# Nixie_clocks_Main_board.net
KiCad netlist of a schematic drawn in Altium Designer
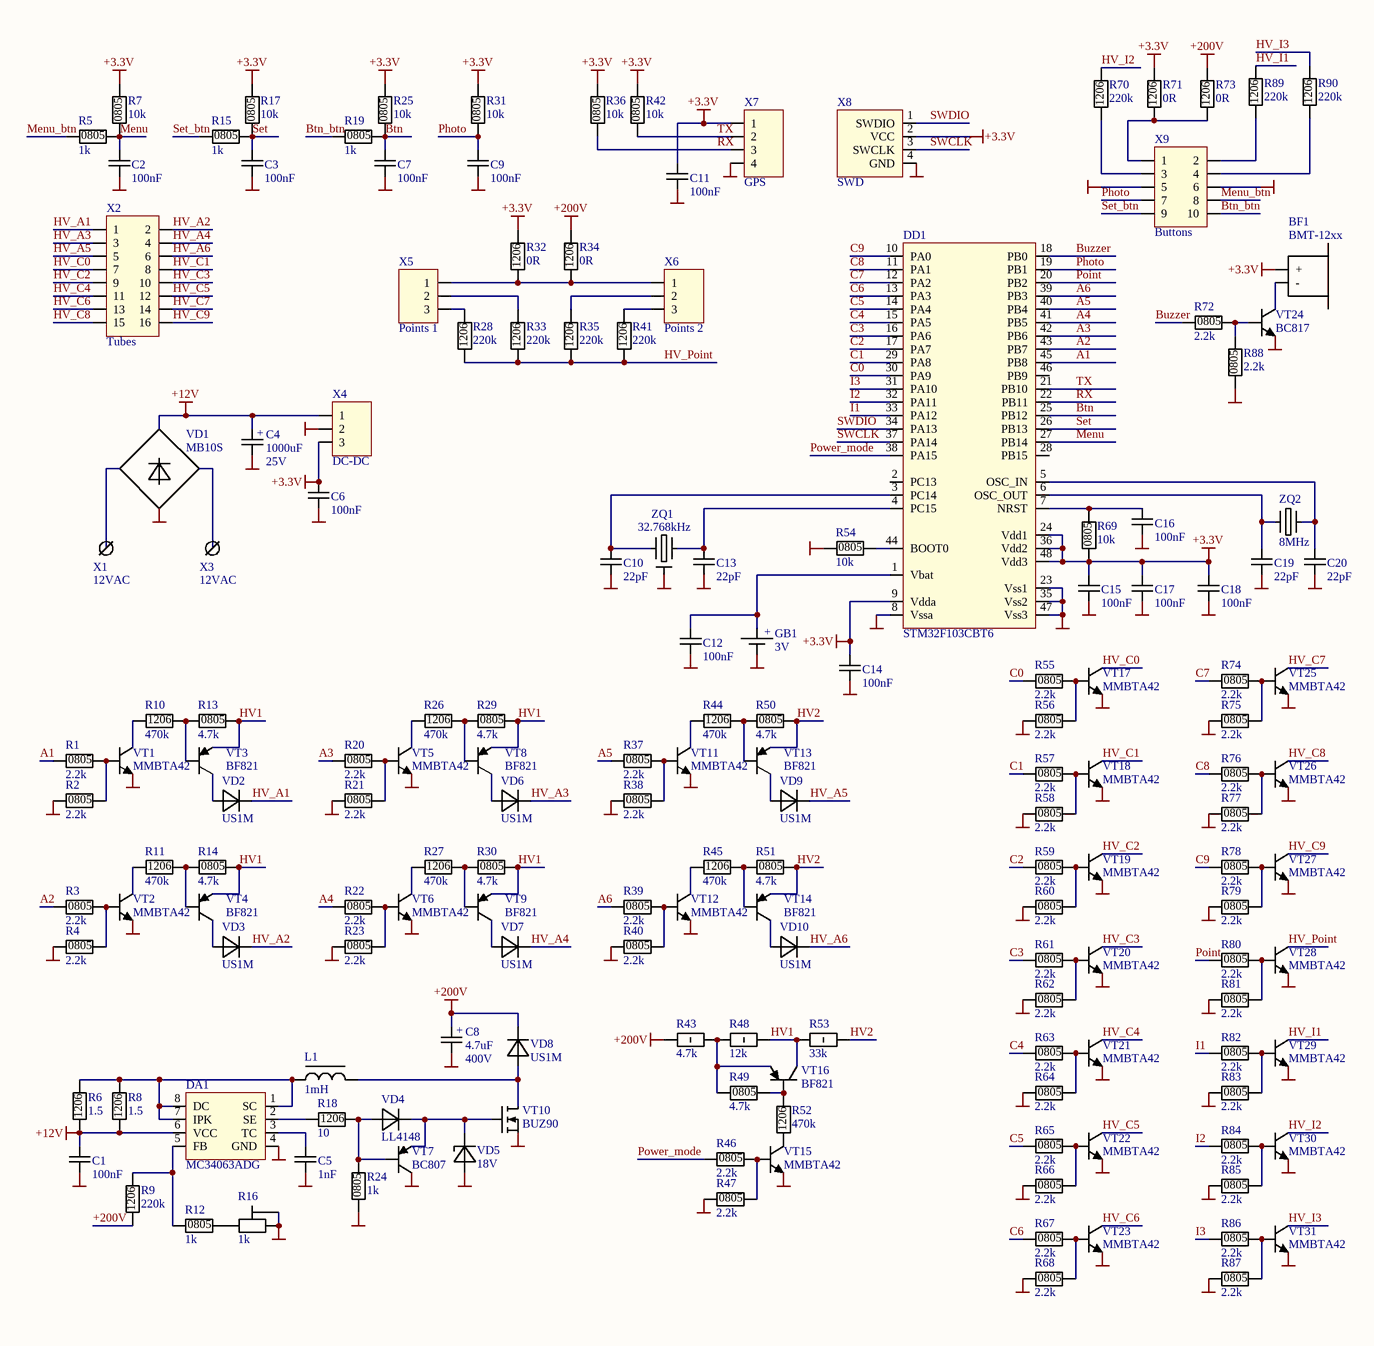
[diagram p0: Nixie_clocks_Main_board.SchDoc]

(export (version "E")
  (design (tool "Eeschema 10.0.6"))
  (components
    (comp (ref "BF1")
      (value "BMT-12xx")
      (footprint "BMT-12xx")
      (description "Magnetic transducer")
      (libsource (lib "Library") (part "Buzzer"))
    )
    (comp (ref "C1")
      (value "100nF")
      (footprint "C0805")
      (description "0805 SMD capacitors")
      (fields (field (name "PART NUMBER") "C0805"))
      (libsource (lib "Library") (part "Capacitor"))
    )
    (comp (ref "C2")
      (value "100nF")
      (footprint "C0805")
      (description "0805 SMD capacitors")
      (fields (field (name "PART NUMBER") "C0805"))
      (libsource (lib "Library") (part "Capacitor"))
    )
    (comp (ref "C3")
      (value "100nF")
      (footprint "C0805")
      (description "0805 SMD capacitors")
      (fields (field (name "PART NUMBER") "C0805"))
      (libsource (lib "Library") (part "Capacitor"))
    )
    (comp (ref "C4")
      (value "1000uF")
      (footprint "CapEl 10x20x5")
      (description "Electrolytic capacitor")
      (fields (field (name "VOLTAGE") "25V") (field (name "PART NUMBER") "CapEL_10x20x5"))
      (libsource (lib "Library") (part "CapEl"))
    )
    (comp (ref "C5")
      (value "1nF")
      (footprint "C0805")
      (description "0805 SMD capacitors")
      (fields (field (name "PART NUMBER") "C0805"))
      (libsource (lib "Library") (part "Capacitor"))
    )
    (comp (ref "C6")
      (value "100nF")
      (footprint "C0805")
      (description "0805 SMD capacitors")
      (fields (field (name "PART NUMBER") "C0805"))
      (libsource (lib "Library") (part "Capacitor"))
    )
    (comp (ref "C7")
      (value "100nF")
      (footprint "C0805")
      (description "0805 SMD capacitors")
      (fields (field (name "PART NUMBER") "C0805"))
      (libsource (lib "Library") (part "Capacitor"))
    )
    (comp (ref "C8")
      (value "4.7uF")
      (footprint "CapEl 10x20x5")
      (description "Electrolytic capacitor")
      (fields (field (name "VOLTAGE") "400V") (field (name "PART NUMBER") "CapEL_10x20x5"))
      (libsource (lib "Library") (part "CapEl"))
    )
    (comp (ref "C9")
      (value "100nF")
      (footprint "C0805")
      (description "0805 SMD capacitors")
      (fields (field (name "PART NUMBER") "C0805"))
      (libsource (lib "Library") (part "Capacitor"))
    )
    (comp (ref "C10")
      (value "22pF")
      (footprint "C0805")
      (description "0805 SMD capacitors")
      (fields (field (name "PART NUMBER") "C0805"))
      (libsource (lib "Library") (part "Capacitor"))
    )
    (comp (ref "C11")
      (value "100nF")
      (footprint "C0805")
      (description "0805 SMD capacitors")
      (fields (field (name "PART NUMBER") "C0805"))
      (libsource (lib "Library") (part "Capacitor"))
    )
    (comp (ref "C12")
      (value "100nF")
      (footprint "C0805")
      (description "0805 SMD capacitors")
      (fields (field (name "PART NUMBER") "C0805"))
      (libsource (lib "Library") (part "Capacitor"))
    )
    (comp (ref "C13")
      (value "22pF")
      (footprint "C0805")
      (description "0805 SMD capacitors")
      (fields (field (name "PART NUMBER") "C0805"))
      (libsource (lib "Library") (part "Capacitor"))
    )
    (comp (ref "C14")
      (value "100nF")
      (footprint "C0805")
      (description "0805 SMD capacitors")
      (fields (field (name "PART NUMBER") "C0805"))
      (libsource (lib "Library") (part "Capacitor"))
    )
    (comp (ref "C15")
      (value "100nF")
      (footprint "C0805")
      (description "0805 SMD capacitors")
      (fields (field (name "PART NUMBER") "C0805"))
      (libsource (lib "Library") (part "Capacitor"))
    )
    (comp (ref "C16")
      (value "100nF")
      (footprint "C0805")
      (description "0805 SMD capacitors")
      (fields (field (name "PART NUMBER") "C0805"))
      (libsource (lib "Library") (part "Capacitor"))
    )
    (comp (ref "C17")
      (value "100nF")
      (footprint "C0805")
      (description "0805 SMD capacitors")
      (fields (field (name "PART NUMBER") "C0805"))
      (libsource (lib "Library") (part "Capacitor"))
    )
    (comp (ref "C18")
      (value "100nF")
      (footprint "C0805")
      (description "0805 SMD capacitors")
      (fields (field (name "PART NUMBER") "C0805"))
      (libsource (lib "Library") (part "Capacitor"))
    )
    (comp (ref "C19")
      (value "22pF")
      (footprint "C0805")
      (description "0805 SMD capacitors")
      (fields (field (name "PART NUMBER") "C0805"))
      (libsource (lib "Library") (part "Capacitor"))
    )
    (comp (ref "C20")
      (value "22pF")
      (footprint "C0805")
      (description "0805 SMD capacitors")
      (fields (field (name "PART NUMBER") "C0805"))
      (libsource (lib "Library") (part "Capacitor"))
    )
    (comp (ref "DA1")
      (value "MC34063ADG")
      (footprint "SO8")
      (description "1.5A, Step-Up/Down/Inverting Switching Regulator")
      (libsource (lib "Library") (part "MC34063"))
    )
    (comp (ref "DD1")
      (value "STM32F103CBT6")
      (footprint "LQFP48")
      (description "ARM Cortex-M3 MCU with 128kB Flash, USB, CAN, etc.")
      (libsource (lib "Library") (part "STM32F103CBT6"))
    )
    (comp (ref "GB1")
      (value "3V")
      (footprint "CH74-2032")
      (description "Lithium CR2032 Vertical THT Battery Holder")
      (fields (field (name "PART NUMBER") "CH74-2032"))
      (libsource (lib "Library") (part "Battery"))
    )
    (comp (ref "L1")
      (value "1mH")
      (footprint "CESL inductor")
      (description "Compact energy-saving lamp inductor")
      (fields (field (name "PART NUMBER") "CESL inductor 1"))
      (libsource (lib "Library") (part "Inductor ferrite 1-4"))
    )
    (comp (ref "R1")
      (value "2.2k")
      (footprint "R0805")
      (description "0805 SMD 1/8W resistor")
      (fields (field (name "PART NUMBER") "R0805"))
      (libsource (lib "Library") (part "Resistor 0805"))
    )
    (comp (ref "R2")
      (value "2.2k")
      (footprint "R0805")
      (description "0805 SMD 1/8W resistor")
      (fields (field (name "PART NUMBER") "R0805"))
      (libsource (lib "Library") (part "Resistor 0805"))
    )
    (comp (ref "R3")
      (value "2.2k")
      (footprint "R0805")
      (description "0805 SMD 1/8W resistor")
      (fields (field (name "PART NUMBER") "R0805"))
      (libsource (lib "Library") (part "Resistor 0805"))
    )
    (comp (ref "R4")
      (value "2.2k")
      (footprint "R0805")
      (description "0805 SMD 1/8W resistor")
      (fields (field (name "PART NUMBER") "R0805"))
      (libsource (lib "Library") (part "Resistor 0805"))
    )
    (comp (ref "R5")
      (value "1k")
      (footprint "R0805")
      (description "0805 SMD 1/8W resistor")
      (fields (field (name "PART NUMBER") "R0805"))
      (libsource (lib "Library") (part "Resistor 0805"))
    )
    (comp (ref "R6")
      (value "1.5")
      (footprint "R1206")
      (description "1206 SMD 1/4W resistor")
      (fields (field (name "PART NUMBER") "R1206"))
      (libsource (lib "Library") (part "Resistor 1206"))
    )
    (comp (ref "R7")
      (value "10k")
      (footprint "R0805")
      (description "0805 SMD 1/8W resistor")
      (fields (field (name "PART NUMBER") "R0805"))
      (libsource (lib "Library") (part "Resistor 0805"))
    )
    (comp (ref "R8")
      (value "1.5")
      (footprint "R1206")
      (description "1206 SMD 1/4W resistor")
      (fields (field (name "PART NUMBER") "R1206"))
      (libsource (lib "Library") (part "Resistor 1206"))
    )
    (comp (ref "R9")
      (value "220k")
      (footprint "R1206")
      (description "1206 SMD 1/4W resistor")
      (fields (field (name "PART NUMBER") "R1206"))
      (libsource (lib "Library") (part "Resistor 1206"))
    )
    (comp (ref "R10")
      (value "470k")
      (footprint "R1206")
      (description "1206 SMD 1/4W resistor")
      (fields (field (name "PART NUMBER") "R1206"))
      (libsource (lib "Library") (part "Resistor 1206"))
    )
    (comp (ref "R11")
      (value "470k")
      (footprint "R1206")
      (description "1206 SMD 1/4W resistor")
      (fields (field (name "PART NUMBER") "R1206"))
      (libsource (lib "Library") (part "Resistor 1206"))
    )
    (comp (ref "R12")
      (value "1k")
      (footprint "R0805")
      (description "0805 SMD 1/8W resistor")
      (fields (field (name "PART NUMBER") "R0805"))
      (libsource (lib "Library") (part "Resistor 0805"))
    )
    (comp (ref "R13")
      (value "4.7k")
      (footprint "R0805")
      (description "0805 SMD 1/8W resistor")
      (fields (field (name "PART NUMBER") "R0805"))
      (libsource (lib "Library") (part "Resistor 0805"))
    )
    (comp (ref "R14")
      (value "4.7k")
      (footprint "R0805")
      (description "0805 SMD 1/8W resistor")
      (fields (field (name "PART NUMBER") "R0805"))
      (libsource (lib "Library") (part "Resistor 0805"))
    )
    (comp (ref "R15")
      (value "1k")
      (footprint "R0805")
      (description "0805 SMD 1/8W resistor")
      (fields (field (name "PART NUMBER") "R0805"))
      (libsource (lib "Library") (part "Resistor 0805"))
    )
    (comp (ref "R16")
      (value "1k")
      (footprint "3296W")
      (description "Multiturn Trimmer Resistor")
      (fields (field (name "PART NUMBER") "3296W"))
      (libsource (lib "Library") (part "Resistor Trimmer"))
    )
    (comp (ref "R17")
      (value "10k")
      (footprint "R0805")
      (description "0805 SMD 1/8W resistor")
      (fields (field (name "PART NUMBER") "R0805"))
      (libsource (lib "Library") (part "Resistor 0805"))
    )
    (comp (ref "R18")
      (value "10")
      (footprint "R1206")
      (description "1206 SMD 1/4W resistor")
      (fields (field (name "PART NUMBER") "R1206"))
      (libsource (lib "Library") (part "Resistor 1206"))
    )
    (comp (ref "R19")
      (value "1k")
      (footprint "R0805")
      (description "0805 SMD 1/8W resistor")
      (fields (field (name "PART NUMBER") "R0805"))
      (libsource (lib "Library") (part "Resistor 0805"))
    )
    (comp (ref "R20")
      (value "2.2k")
      (footprint "R0805")
      (description "0805 SMD 1/8W resistor")
      (fields (field (name "PART NUMBER") "R0805"))
      (libsource (lib "Library") (part "Resistor 0805"))
    )
    (comp (ref "R21")
      (value "2.2k")
      (footprint "R0805")
      (description "0805 SMD 1/8W resistor")
      (fields (field (name "PART NUMBER") "R0805"))
      (libsource (lib "Library") (part "Resistor 0805"))
    )
    (comp (ref "R22")
      (value "2.2k")
      (footprint "R0805")
      (description "0805 SMD 1/8W resistor")
      (fields (field (name "PART NUMBER") "R0805"))
      (libsource (lib "Library") (part "Resistor 0805"))
    )
    (comp (ref "R23")
      (value "2.2k")
      (footprint "R0805")
      (description "0805 SMD 1/8W resistor")
      (fields (field (name "PART NUMBER") "R0805"))
      (libsource (lib "Library") (part "Resistor 0805"))
    )
    (comp (ref "R24")
      (value "1k")
      (footprint "R0805")
      (description "0805 SMD 1/8W resistor")
      (fields (field (name "PART NUMBER") "R0805"))
      (libsource (lib "Library") (part "Resistor 0805"))
    )
    (comp (ref "R25")
      (value "10k")
      (footprint "R0805")
      (description "0805 SMD 1/8W resistor")
      (fields (field (name "PART NUMBER") "R0805"))
      (libsource (lib "Library") (part "Resistor 0805"))
    )
    (comp (ref "R26")
      (value "470k")
      (footprint "R1206")
      (description "1206 SMD 1/4W resistor")
      (fields (field (name "PART NUMBER") "R1206"))
      (libsource (lib "Library") (part "Resistor 1206"))
    )
    (comp (ref "R27")
      (value "470k")
      (footprint "R1206")
      (description "1206 SMD 1/4W resistor")
      (fields (field (name "PART NUMBER") "R1206"))
      (libsource (lib "Library") (part "Resistor 1206"))
    )
    (comp (ref "R28")
      (value "220k")
      (footprint "R1206")
      (description "1206 SMD 1/4W resistor")
      (fields (field (name "PART NUMBER") "R1206"))
      (libsource (lib "Library") (part "Resistor 1206"))
    )
    (comp (ref "R29")
      (value "4.7k")
      (footprint "R0805")
      (description "0805 SMD 1/8W resistor")
      (fields (field (name "PART NUMBER") "R0805"))
      (libsource (lib "Library") (part "Resistor 0805"))
    )
    (comp (ref "R30")
      (value "4.7k")
      (footprint "R0805")
      (description "0805 SMD 1/8W resistor")
      (fields (field (name "PART NUMBER") "R0805"))
      (libsource (lib "Library") (part "Resistor 0805"))
    )
    (comp (ref "R31")
      (value "10k")
      (footprint "R0805")
      (description "0805 SMD 1/8W resistor")
      (fields (field (name "PART NUMBER") "R0805"))
      (libsource (lib "Library") (part "Resistor 0805"))
    )
    (comp (ref "R32")
      (value "0R")
      (footprint "R1206")
      (description "1206 SMD 1/4W resistor")
      (fields (field (name "PART NUMBER") "R1206"))
      (libsource (lib "Library") (part "Resistor 1206"))
    )
    (comp (ref "R33")
      (value "220k")
      (footprint "R1206")
      (description "1206 SMD 1/4W resistor")
      (fields (field (name "PART NUMBER") "R1206"))
      (libsource (lib "Library") (part "Resistor 1206"))
    )
    (comp (ref "R34")
      (value "0R")
      (footprint "R1206")
      (description "1206 SMD 1/4W resistor")
      (fields (field (name "PART NUMBER") "R1206"))
      (libsource (lib "Library") (part "Resistor 1206"))
    )
    (comp (ref "R35")
      (value "220k")
      (footprint "R1206")
      (description "1206 SMD 1/4W resistor")
      (fields (field (name "PART NUMBER") "R1206"))
      (libsource (lib "Library") (part "Resistor 1206"))
    )
    (comp (ref "R36")
      (value "10k")
      (footprint "R0805")
      (description "0805 SMD 1/8W resistor")
      (fields (field (name "PART NUMBER") "R0805"))
      (libsource (lib "Library") (part "Resistor 0805"))
    )
    (comp (ref "R37")
      (value "2.2k")
      (footprint "R0805")
      (description "0805 SMD 1/8W resistor")
      (fields (field (name "PART NUMBER") "R0805"))
      (libsource (lib "Library") (part "Resistor 0805"))
    )
    (comp (ref "R38")
      (value "2.2k")
      (footprint "R0805")
      (description "0805 SMD 1/8W resistor")
      (fields (field (name "PART NUMBER") "R0805"))
      (libsource (lib "Library") (part "Resistor 0805"))
    )
    (comp (ref "R39")
      (value "2.2k")
      (footprint "R0805")
      (description "0805 SMD 1/8W resistor")
      (fields (field (name "PART NUMBER") "R0805"))
      (libsource (lib "Library") (part "Resistor 0805"))
    )
    (comp (ref "R40")
      (value "2.2k")
      (footprint "R0805")
      (description "0805 SMD 1/8W resistor")
      (fields (field (name "PART NUMBER") "R0805"))
      (libsource (lib "Library") (part "Resistor 0805"))
    )
    (comp (ref "R41")
      (value "220k")
      (footprint "R1206")
      (description "1206 SMD 1/4W resistor")
      (fields (field (name "PART NUMBER") "R1206"))
      (libsource (lib "Library") (part "Resistor 1206"))
    )
    (comp (ref "R42")
      (value "10k")
      (footprint "R0805")
      (description "0805 SMD 1/8W resistor")
      (fields (field (name "PART NUMBER") "R0805"))
      (libsource (lib "Library") (part "Resistor 0805"))
    )
    (comp (ref "R43")
      (value "4.7k")
      (footprint "MF-1W Vertical")
      (description "1W THT Resistor (Vertical mounting)")
      (fields (field (name "PART NUMBER") "MF-1WV"))
      (libsource (lib "Library") (part "Resistor 1W"))
    )
    (comp (ref "R44")
      (value "470k")
      (footprint "R1206")
      (description "1206 SMD 1/4W resistor")
      (fields (field (name "PART NUMBER") "R1206"))
      (libsource (lib "Library") (part "Resistor 1206"))
    )
    (comp (ref "R45")
      (value "470k")
      (footprint "R1206")
      (description "1206 SMD 1/4W resistor")
      (fields (field (name "PART NUMBER") "R1206"))
      (libsource (lib "Library") (part "Resistor 1206"))
    )
    (comp (ref "R46")
      (value "2.2k")
      (footprint "R0805")
      (description "0805 SMD 1/8W resistor")
      (fields (field (name "PART NUMBER") "R0805"))
      (libsource (lib "Library") (part "Resistor 0805"))
    )
    (comp (ref "R47")
      (value "2.2k")
      (footprint "R0805")
      (description "0805 SMD 1/8W resistor")
      (fields (field (name "PART NUMBER") "R0805"))
      (libsource (lib "Library") (part "Resistor 0805"))
    )
    (comp (ref "R48")
      (value "12k")
      (footprint "MF-1W Vertical")
      (description "1W THT Resistor (Vertical mounting)")
      (fields (field (name "PART NUMBER") "MF-1WV"))
      (libsource (lib "Library") (part "Resistor 1W"))
    )
    (comp (ref "R49")
      (value "4.7k")
      (footprint "R0805")
      (description "0805 SMD 1/8W resistor")
      (fields (field (name "PART NUMBER") "R0805"))
      (libsource (lib "Library") (part "Resistor 0805"))
    )
    (comp (ref "R50")
      (value "4.7k")
      (footprint "R0805")
      (description "0805 SMD 1/8W resistor")
      (fields (field (name "PART NUMBER") "R0805"))
      (libsource (lib "Library") (part "Resistor 0805"))
    )
    (comp (ref "R51")
      (value "4.7k")
      (footprint "R0805")
      (description "0805 SMD 1/8W resistor")
      (fields (field (name "PART NUMBER") "R0805"))
      (libsource (lib "Library") (part "Resistor 0805"))
    )
    (comp (ref "R52")
      (value "470k")
      (footprint "R1206")
      (description "1206 SMD 1/4W resistor")
      (fields (field (name "PART NUMBER") "R1206"))
      (libsource (lib "Library") (part "Resistor 1206"))
    )
    (comp (ref "R53")
      (value "33k")
      (footprint "MF-1W Vertical")
      (description "1W THT Resistor (Vertical mounting)")
      (fields (field (name "PART NUMBER") "MF-1WV"))
      (libsource (lib "Library") (part "Resistor 1W"))
    )
    (comp (ref "R54")
      (value "10k")
      (footprint "R0805")
      (description "0805 SMD 1/8W resistor")
      (fields (field (name "PART NUMBER") "R0805"))
      (libsource (lib "Library") (part "Resistor 0805"))
    )
    (comp (ref "R55")
      (value "2.2k")
      (footprint "R0805")
      (description "0805 SMD 1/8W resistor")
      (fields (field (name "PART NUMBER") "R0805"))
      (libsource (lib "Library") (part "Resistor 0805"))
    )
    (comp (ref "R56")
      (value "2.2k")
      (footprint "R0805")
      (description "0805 SMD 1/8W resistor")
      (fields (field (name "PART NUMBER") "R0805"))
      (libsource (lib "Library") (part "Resistor 0805"))
    )
    (comp (ref "R57")
      (value "2.2k")
      (footprint "R0805")
      (description "0805 SMD 1/8W resistor")
      (fields (field (name "PART NUMBER") "R0805"))
      (libsource (lib "Library") (part "Resistor 0805"))
    )
    (comp (ref "R58")
      (value "2.2k")
      (footprint "R0805")
      (description "0805 SMD 1/8W resistor")
      (fields (field (name "PART NUMBER") "R0805"))
      (libsource (lib "Library") (part "Resistor 0805"))
    )
    (comp (ref "R59")
      (value "2.2k")
      (footprint "R0805")
      (description "0805 SMD 1/8W resistor")
      (fields (field (name "PART NUMBER") "R0805"))
      (libsource (lib "Library") (part "Resistor 0805"))
    )
    (comp (ref "R60")
      (value "2.2k")
      (footprint "R0805")
      (description "0805 SMD 1/8W resistor")
      (fields (field (name "PART NUMBER") "R0805"))
      (libsource (lib "Library") (part "Resistor 0805"))
    )
    (comp (ref "R61")
      (value "2.2k")
      (footprint "R0805")
      (description "0805 SMD 1/8W resistor")
      (fields (field (name "PART NUMBER") "R0805"))
      (libsource (lib "Library") (part "Resistor 0805"))
    )
    (comp (ref "R62")
      (value "2.2k")
      (footprint "R0805")
      (description "0805 SMD 1/8W resistor")
      (fields (field (name "PART NUMBER") "R0805"))
      (libsource (lib "Library") (part "Resistor 0805"))
    )
    (comp (ref "R63")
      (value "2.2k")
      (footprint "R0805")
      (description "0805 SMD 1/8W resistor")
      (fields (field (name "PART NUMBER") "R0805"))
      (libsource (lib "Library") (part "Resistor 0805"))
    )
    (comp (ref "R64")
      (value "2.2k")
      (footprint "R0805")
      (description "0805 SMD 1/8W resistor")
      (fields (field (name "PART NUMBER") "R0805"))
      (libsource (lib "Library") (part "Resistor 0805"))
    )
    (comp (ref "R65")
      (value "2.2k")
      (footprint "R0805")
      (description "0805 SMD 1/8W resistor")
      (fields (field (name "PART NUMBER") "R0805"))
      (libsource (lib "Library") (part "Resistor 0805"))
    )
    (comp (ref "R66")
      (value "2.2k")
      (footprint "R0805")
      (description "0805 SMD 1/8W resistor")
      (fields (field (name "PART NUMBER") "R0805"))
      (libsource (lib "Library") (part "Resistor 0805"))
    )
    (comp (ref "R67")
      (value "2.2k")
      (footprint "R0805")
      (description "0805 SMD 1/8W resistor")
      (fields (field (name "PART NUMBER") "R0805"))
      (libsource (lib "Library") (part "Resistor 0805"))
    )
    (comp (ref "R68")
      (value "2.2k")
      (footprint "R0805")
      (description "0805 SMD 1/8W resistor")
      (fields (field (name "PART NUMBER") "R0805"))
      (libsource (lib "Library") (part "Resistor 0805"))
    )
    (comp (ref "R69")
      (value "10k")
      (footprint "R0805")
      (description "0805 SMD 1/8W resistor")
      (fields (field (name "PART NUMBER") "R0805"))
      (libsource (lib "Library") (part "Resistor 0805"))
    )
    (comp (ref "R70")
      (value "220k")
      (footprint "R1206")
      (description "1206 SMD 1/4W resistor")
      (fields (field (name "PART NUMBER") "R1206"))
      (libsource (lib "Library") (part "Resistor 1206"))
    )
    (comp (ref "R71")
      (value "0R")
      (footprint "R1206")
      (description "1206 SMD 1/4W resistor")
      (fields (field (name "PART NUMBER") "R1206"))
      (libsource (lib "Library") (part "Resistor 1206"))
    )
    (comp (ref "R72")
      (value "2.2k")
      (footprint "R0805")
      (description "0805 SMD 1/8W resistor")
      (fields (field (name "PART NUMBER") "R0805"))
      (libsource (lib "Library") (part "Resistor 0805"))
    )
    (comp (ref "R73")
      (value "0R")
      (footprint "R1206")
      (description "1206 SMD 1/4W resistor")
      (fields (field (name "PART NUMBER") "R1206"))
      (libsource (lib "Library") (part "Resistor 1206"))
    )
    (comp (ref "R74")
      (value "2.2k")
      (footprint "R0805")
      (description "0805 SMD 1/8W resistor")
      (fields (field (name "PART NUMBER") "R0805"))
      (libsource (lib "Library") (part "Resistor 0805"))
    )
    (comp (ref "R75")
      (value "2.2k")
      (footprint "R0805")
      (description "0805 SMD 1/8W resistor")
      (fields (field (name "PART NUMBER") "R0805"))
      (libsource (lib "Library") (part "Resistor 0805"))
    )
    (comp (ref "R76")
      (value "2.2k")
      (footprint "R0805")
      (description "0805 SMD 1/8W resistor")
      (fields (field (name "PART NUMBER") "R0805"))
      (libsource (lib "Library") (part "Resistor 0805"))
    )
    (comp (ref "R77")
      (value "2.2k")
      (footprint "R0805")
      (description "0805 SMD 1/8W resistor")
      (fields (field (name "PART NUMBER") "R0805"))
      (libsource (lib "Library") (part "Resistor 0805"))
    )
    (comp (ref "R78")
      (value "2.2k")
      (footprint "R0805")
      (description "0805 SMD 1/8W resistor")
      (fields (field (name "PART NUMBER") "R0805"))
      (libsource (lib "Library") (part "Resistor 0805"))
    )
    (comp (ref "R79")
      (value "2.2k")
      (footprint "R0805")
      (description "0805 SMD 1/8W resistor")
      (fields (field (name "PART NUMBER") "R0805"))
      (libsource (lib "Library") (part "Resistor 0805"))
    )
    (comp (ref "R80")
      (value "2.2k")
      (footprint "R0805")
      (description "0805 SMD 1/8W resistor")
      (fields (field (name "PART NUMBER") "R0805"))
      (libsource (lib "Library") (part "Resistor 0805"))
    )
    (comp (ref "R81")
      (value "2.2k")
      (footprint "R0805")
      (description "0805 SMD 1/8W resistor")
      (fields (field (name "PART NUMBER") "R0805"))
      (libsource (lib "Library") (part "Resistor 0805"))
    )
    (comp (ref "R82")
      (value "2.2k")
      (footprint "R0805")
      (description "0805 SMD 1/8W resistor")
      (fields (field (name "PART NUMBER") "R0805"))
      (libsource (lib "Library") (part "Resistor 0805"))
    )
    (comp (ref "R83")
      (value "2.2k")
      (footprint "R0805")
      (description "0805 SMD 1/8W resistor")
      (fields (field (name "PART NUMBER") "R0805"))
      (libsource (lib "Library") (part "Resistor 0805"))
    )
    (comp (ref "R84")
      (value "2.2k")
      (footprint "R0805")
      (description "0805 SMD 1/8W resistor")
      (fields (field (name "PART NUMBER") "R0805"))
      (libsource (lib "Library") (part "Resistor 0805"))
    )
    (comp (ref "R85")
      (value "2.2k")
      (footprint "R0805")
      (description "0805 SMD 1/8W resistor")
      (fields (field (name "PART NUMBER") "R0805"))
      (libsource (lib "Library") (part "Resistor 0805"))
    )
    (comp (ref "R86")
      (value "2.2k")
      (footprint "R0805")
      (description "0805 SMD 1/8W resistor")
      (fields (field (name "PART NUMBER") "R0805"))
      (libsource (lib "Library") (part "Resistor 0805"))
    )
    (comp (ref "R87")
      (value "2.2k")
      (footprint "R0805")
      (description "0805 SMD 1/8W resistor")
      (fields (field (name "PART NUMBER") "R0805"))
      (libsource (lib "Library") (part "Resistor 0805"))
    )
    (comp (ref "R88")
      (value "2.2k")
      (footprint "R0805")
      (description "0805 SMD 1/8W resistor")
      (fields (field (name "PART NUMBER") "R0805"))
      (libsource (lib "Library") (part "Resistor 0805"))
    )
    (comp (ref "R89")
      (value "220k")
      (footprint "R1206")
      (description "1206 SMD 1/4W resistor")
      (fields (field (name "PART NUMBER") "R1206"))
      (libsource (lib "Library") (part "Resistor 1206"))
    )
    (comp (ref "R90")
      (value "220k")
      (footprint "R1206")
      (description "1206 SMD 1/4W resistor")
      (fields (field (name "PART NUMBER") "R1206"))
      (libsource (lib "Library") (part "Resistor 1206"))
    )
    (comp (ref "VD1")
      (value "MB10S")
      (footprint "MBS")
      (description "Single-Phase Silicon Bridge Rectifier")
      (libsource (lib "Library") (part "Diode Bridge"))
    )
    (comp (ref "VD2")
      (value "US1M")
      (footprint "SMA")
      (description "Surface Mount Ultrafast Rectifier")
      (libsource (lib "Library") (part "Diode"))
    )
    (comp (ref "VD3")
      (value "US1M")
      (footprint "SMA")
      (description "Surface Mount Ultrafast Rectifier")
      (libsource (lib "Library") (part "Diode"))
    )
    (comp (ref "VD4")
      (value "LL4148")
      (footprint "SOD80")
      (description "75V 150mA Small Signal Fast Switching Diode")
      (libsource (lib "Library") (part "Diode"))
    )
    (comp (ref "VD5")
      (value "18V")
      (footprint "SOD80")
      (description "500mW SMD Zener Diode")
      (fields (field (name "PART NUMBER") "BZV55"))
      (libsource (lib "Library") (part "Diode Zener"))
    )
    (comp (ref "VD6")
      (value "US1M")
      (footprint "SMA")
      (description "Surface Mount Ultrafast Rectifier")
      (libsource (lib "Library") (part "Diode"))
    )
    (comp (ref "VD7")
      (value "US1M")
      (footprint "SMA")
      (description "Surface Mount Ultrafast Rectifier")
      (libsource (lib "Library") (part "Diode"))
    )
    (comp (ref "VD8")
      (value "US1M")
      (footprint "SMA")
      (description "Surface Mount Ultrafast Rectifier")
      (libsource (lib "Library") (part "Diode"))
    )
    (comp (ref "VD9")
      (value "US1M")
      (footprint "SMA")
      (description "Surface Mount Ultrafast Rectifier")
      (libsource (lib "Library") (part "Diode"))
    )
    (comp (ref "VD10")
      (value "US1M")
      (footprint "SMA")
      (description "Surface Mount Ultrafast Rectifier")
      (libsource (lib "Library") (part "Diode"))
    )
    (comp (ref "VT1")
      (value "MMBTA42")
      (footprint "SOT23-3")
      (description "300V 500mA SOT23-3 SMD NPN transistor with h21>25")
      (libsource (lib "Library") (part "NPN_BEC"))
    )
    (comp (ref "VT2")
      (value "MMBTA42")
      (footprint "SOT23-3")
      (description "300V 500mA SOT23-3 SMD NPN transistor with h21>25")
      (libsource (lib "Library") (part "NPN_BEC"))
    )
    (comp (ref "VT3")
      (value "BF821")
      (footprint "SOT23-3")
      (description "300V 50mA SOT23-3 SMD PNP transistor with h21>50")
      (libsource (lib "Library") (part "PNP_BEC"))
    )
    (comp (ref "VT4")
      (value "BF821")
      (footprint "SOT23-3")
      (description "300V 50mA SOT23-3 SMD PNP transistor with h21>50")
      (libsource (lib "Library") (part "PNP_BEC"))
    )
    (comp (ref "VT5")
      (value "MMBTA42")
      (footprint "SOT23-3")
      (description "300V 500mA SOT23-3 SMD NPN transistor with h21>25")
      (libsource (lib "Library") (part "NPN_BEC"))
    )
    (comp (ref "VT6")
      (value "MMBTA42")
      (footprint "SOT23-3")
      (description "300V 500mA SOT23-3 SMD NPN transistor with h21>25")
      (libsource (lib "Library") (part "NPN_BEC"))
    )
    (comp (ref "VT7")
      (value "BC807")
      (footprint "SOT23-3")
      (description "45V 500mA SOT23-3 SMD PNP transistor with h21>100")
      (libsource (lib "Library") (part "PNP_BEC"))
    )
    (comp (ref "VT8")
      (value "BF821")
      (footprint "SOT23-3")
      (description "300V 50mA SOT23-3 SMD PNP transistor with h21>50")
      (libsource (lib "Library") (part "PNP_BEC"))
    )
    (comp (ref "VT9")
      (value "BF821")
      (footprint "SOT23-3")
      (description "300V 50mA SOT23-3 SMD PNP transistor with h21>50")
      (libsource (lib "Library") (part "PNP_BEC"))
    )
    (comp (ref "VT10")
      (value "BUZ90")
      (footprint "TO220-3")
      (description "600V 4.5A TO220-3 THT n-MOSFET transistor")
      (libsource (lib "Library") (part "NMOSFET_GDS"))
    )
    (comp (ref "VT11")
      (value "MMBTA42")
      (footprint "SOT23-3")
      (description "300V 500mA SOT23-3 SMD NPN transistor with h21>25")
      (libsource (lib "Library") (part "NPN_BEC"))
    )
    (comp (ref "VT12")
      (value "MMBTA42")
      (footprint "SOT23-3")
      (description "300V 500mA SOT23-3 SMD NPN transistor with h21>25")
      (libsource (lib "Library") (part "NPN_BEC"))
    )
    (comp (ref "VT13")
      (value "BF821")
      (footprint "SOT23-3")
      (description "300V 50mA SOT23-3 SMD PNP transistor with h21>50")
      (libsource (lib "Library") (part "PNP_BEC"))
    )
    (comp (ref "VT14")
      (value "BF821")
      (footprint "SOT23-3")
      (description "300V 50mA SOT23-3 SMD PNP transistor with h21>50")
      (libsource (lib "Library") (part "PNP_BEC"))
    )
    (comp (ref "VT15")
      (value "MMBTA42")
      (footprint "SOT23-3")
      (description "300V 500mA SOT23-3 SMD NPN transistor with h21>25")
      (libsource (lib "Library") (part "NPN_BEC"))
    )
    (comp (ref "VT16")
      (value "BF821")
      (footprint "SOT23-3")
      (description "300V 50mA SOT23-3 SMD PNP transistor with h21>50")
      (libsource (lib "Library") (part "PNP_BEC"))
    )
    (comp (ref "VT17")
      (value "MMBTA42")
      (footprint "SOT23-3")
      (description "300V 500mA SOT23-3 SMD NPN transistor with h21>25")
      (libsource (lib "Library") (part "NPN_BEC"))
    )
    (comp (ref "VT18")
      (value "MMBTA42")
      (footprint "SOT23-3")
      (description "300V 500mA SOT23-3 SMD NPN transistor with h21>25")
      (libsource (lib "Library") (part "NPN_BEC"))
    )
    (comp (ref "VT19")
      (value "MMBTA42")
      (footprint "SOT23-3")
      (description "300V 500mA SOT23-3 SMD NPN transistor with h21>25")
      (libsource (lib "Library") (part "NPN_BEC"))
    )
    (comp (ref "VT20")
      (value "MMBTA42")
      (footprint "SOT23-3")
      (description "300V 500mA SOT23-3 SMD NPN transistor with h21>25")
      (libsource (lib "Library") (part "NPN_BEC"))
    )
    (comp (ref "VT21")
      (value "MMBTA42")
      (footprint "SOT23-3")
      (description "300V 500mA SOT23-3 SMD NPN transistor with h21>25")
      (libsource (lib "Library") (part "NPN_BEC"))
    )
    (comp (ref "VT22")
      (value "MMBTA42")
      (footprint "SOT23-3")
      (description "300V 500mA SOT23-3 SMD NPN transistor with h21>25")
      (libsource (lib "Library") (part "NPN_BEC"))
    )
    (comp (ref "VT23")
      (value "MMBTA42")
      (footprint "SOT23-3")
      (description "300V 500mA SOT23-3 SMD NPN transistor with h21>25")
      (libsource (lib "Library") (part "NPN_BEC"))
    )
    (comp (ref "VT24")
      (value "BC817")
      (footprint "SOT23-3")
      (description "45V 500mA SOT23-3 SMD NPN transistor with h21>100")
      (libsource (lib "Library") (part "NPN_BEC"))
    )
    (comp (ref "VT25")
      (value "MMBTA42")
      (footprint "SOT23-3")
      (description "300V 500mA SOT23-3 SMD NPN transistor with h21>25")
      (libsource (lib "Library") (part "NPN_BEC"))
    )
    (comp (ref "VT26")
      (value "MMBTA42")
      (footprint "SOT23-3")
      (description "300V 500mA SOT23-3 SMD NPN transistor with h21>25")
      (libsource (lib "Library") (part "NPN_BEC"))
    )
    (comp (ref "VT27")
      (value "MMBTA42")
      (footprint "SOT23-3")
      (description "300V 500mA SOT23-3 SMD NPN transistor with h21>25")
      (libsource (lib "Library") (part "NPN_BEC"))
    )
    (comp (ref "VT28")
      (value "MMBTA42")
      (footprint "SOT23-3")
      (description "300V 500mA SOT23-3 SMD NPN transistor with h21>25")
      (libsource (lib "Library") (part "NPN_BEC"))
    )
    (comp (ref "VT29")
      (value "MMBTA42")
      (footprint "SOT23-3")
      (description "300V 500mA SOT23-3 SMD NPN transistor with h21>25")
      (libsource (lib "Library") (part "NPN_BEC"))
    )
    (comp (ref "VT30")
      (value "MMBTA42")
      (footprint "SOT23-3")
      (description "300V 500mA SOT23-3 SMD NPN transistor with h21>25")
      (libsource (lib "Library") (part "NPN_BEC"))
    )
    (comp (ref "VT31")
      (value "MMBTA42")
      (footprint "SOT23-3")
      (description "300V 500mA SOT23-3 SMD NPN transistor with h21>25")
      (libsource (lib "Library") (part "NPN_BEC"))
    )
    (comp (ref "X1")
      (value "12VAC")
      (footprint "Terminal_2,8")
      (description "Terminal")
      (fields (field (name "PART NUMBER") "Term_2.8"))
      (libsource (lib "Library") (part "Terminal"))
    )
    (comp (ref "X2")
      (value "Tubes")
      (footprint "IDC16")
      (description "PCB Connector")
      (fields (field (name "PART NUMBER") "IDC-16"))
      (libsource (lib "Library") (part "IDC16"))
    )
    (comp (ref "X3")
      (value "12VAC")
      (footprint "Terminal_2,8")
      (description "Terminal")
      (fields (field (name "PART NUMBER") "Term_2.8"))
      (libsource (lib "Library") (part "Terminal"))
    )
    (comp (ref "X4")
      (value "DC-DC")
      (footprint "PBS3")
      (description "PCB Connector")
      (fields (field (name "PART NUMBER") "PBS-3"))
      (libsource (lib "Library") (part "Connector 3 pin"))
    )
    (comp (ref "X5")
      (value "Points 1")
      (footprint "WF-3")
      (description "PCB Connector")
      (fields (field (name "PART NUMBER") "WF-3"))
      (libsource (lib "") (part "Connector 3 pin_1"))
    )
    (comp (ref "X6")
      (value "Points 2")
      (footprint "WF-3")
      (description "PCB Connector")
      (fields (field (name "PART NUMBER") "WF-3"))
      (libsource (lib "Library") (part "Connector 3 pin"))
    )
    (comp (ref "X7")
      (value "GPS")
      (footprint "WF-4")
      (description "PCB Connector")
      (fields (field (name "PART NUMBER") "WF-4"))
      (libsource (lib "Library") (part "Connector 4 pin"))
    )
    (comp (ref "X8")
      (value "SWD")
      (footprint "PLS4")
      (description "4 pin SWD connector for ARM MCU programming")
      (libsource (lib "Library") (part "Connector SWD"))
    )
    (comp (ref "X9")
      (value "Buttons")
      (footprint "IDC10")
      (description "PCB Connector")
      (fields (field (name "PART NUMBER") "IDC-10"))
      (libsource (lib "Library") (part "IDC10"))
    )
    (comp (ref "ZQ1")
      (value "32.768kHz")
      (footprint "DT-38")
      (description "RTC THT Quartz Resonator")
      (fields (field (name "PART NUMBER") "DT-38"))
      (libsource (lib "Library") (part "Quartz grounded"))
    )
    (comp (ref "ZQ2")
      (value "8MHz")
      (footprint "HC49SM")
      (description "Standard SMD Quartz Resonator")
      (fields (field (name "PART NUMBER") "HC49SM"))
      (libsource (lib "Library") (part "Quartz"))
    )
  )
  (nets
    (net (code "1") (name "+3.3V") (class "Default")
      (node (ref "BF1") (pin "1") (pinfunction "+_1") (pintype "passive"))
      (node (ref "C11") (pin "2") (pinfunction "2_2") (pintype "passive"))
      (node (ref "C14") (pin "2") (pinfunction "2_2") (pintype "passive"))
      (node (ref "C15") (pin "2") (pinfunction "2_2") (pintype "passive"))
      (node (ref "C17") (pin "2") (pinfunction "2_2") (pintype "passive"))
      (node (ref "C18") (pin "2") (pinfunction "2_2") (pintype "passive"))
      (node (ref "C6") (pin "2") (pinfunction "2_2") (pintype "passive"))
      (node (ref "DD1") (pin "24") (pinfunction "Vdd1_24") (pintype "passive"))
      (node (ref "DD1") (pin "36") (pinfunction "Vdd2_36") (pintype "passive"))
      (node (ref "DD1") (pin "48") (pinfunction "Vdd3_48") (pintype "passive"))
      (node (ref "DD1") (pin "9") (pinfunction "Vdda_9") (pintype "passive"))
      (node (ref "R17") (pin "2") (pinfunction "2_2") (pintype "passive"))
      (node (ref "R25") (pin "2") (pinfunction "2_2") (pintype "passive"))
      (node (ref "R31") (pin "2") (pinfunction "2_2") (pintype "passive"))
      (node (ref "R32") (pin "2") (pinfunction "2_2") (pintype "passive"))
      (node (ref "R36") (pin "2") (pinfunction "2_2") (pintype "passive"))
      (node (ref "R42") (pin "2") (pinfunction "2_2") (pintype "passive"))
      (node (ref "R69") (pin "1") (pinfunction "1_1") (pintype "passive"))
      (node (ref "R7") (pin "2") (pinfunction "2_2") (pintype "passive"))
      (node (ref "R71") (pin "2") (pinfunction "2_2") (pintype "passive"))
      (node (ref "X4") (pin "3") (pinfunction "3_3") (pintype "passive"))
      (node (ref "X7") (pin "1") (pinfunction "1_1") (pintype "passive"))
      (node (ref "X8") (pin "2") (pinfunction "VCC_2") (pintype "passive"))
    )
    (net (code "2") (name "+12V") (class "Default")
      (node (ref "C1") (pin "2") (pinfunction "2_2") (pintype "passive"))
      (node (ref "C4") (pin "1") (pinfunction "1_1") (pintype "passive"))
      (node (ref "DA1") (pin "6") (pinfunction "VCC_6") (pintype "passive"))
      (node (ref "R6") (pin "1") (pinfunction "1_1") (pintype "passive"))
      (node (ref "R8") (pin "1") (pinfunction "1_1") (pintype "passive"))
      (node (ref "VD1") (pin "1") (pinfunction "+U_1") (pintype "passive"))
      (node (ref "X4") (pin "1") (pinfunction "1_1") (pintype "passive"))
    )
    (net (code "3") (name "+200V") (class "Default")
      (node (ref "C8") (pin "1") (pinfunction "1_1") (pintype "passive"))
      (node (ref "R34") (pin "2") (pinfunction "2_2") (pintype "passive"))
      (node (ref "R43") (pin "1") (pinfunction "1_1") (pintype "passive"))
      (node (ref "R73") (pin "2") (pinfunction "2_2") (pintype "passive"))
      (node (ref "R9") (pin "1") (pinfunction "1_1") (pintype "passive"))
      (node (ref "VD8") (pin "2") (pinfunction "K_2") (pintype "passive"))
    )
    (net (code "4") (name "/A1") (class "Default")
      (node (ref "DD1") (pin "45") (pinfunction "PB8_45") (pintype "passive"))
      (node (ref "R1") (pin "1") (pinfunction "1_1") (pintype "passive"))
    )
    (net (code "5") (name "/A2") (class "Default")
      (node (ref "DD1") (pin "43") (pinfunction "PB7_43") (pintype "passive"))
      (node (ref "R3") (pin "1") (pinfunction "1_1") (pintype "passive"))
    )
    (net (code "6") (name "/A3") (class "Default")
      (node (ref "DD1") (pin "42") (pinfunction "PB6_42") (pintype "passive"))
      (node (ref "R20") (pin "1") (pinfunction "1_1") (pintype "passive"))
    )
    (net (code "7") (name "/A4") (class "Default")
      (node (ref "DD1") (pin "41") (pinfunction "PB5_41") (pintype "passive"))
      (node (ref "R22") (pin "1") (pinfunction "1_1") (pintype "passive"))
    )
    (net (code "8") (name "/A5") (class "Default")
      (node (ref "DD1") (pin "40") (pinfunction "PB4_40") (pintype "passive"))
      (node (ref "R37") (pin "1") (pinfunction "1_1") (pintype "passive"))
    )
    (net (code "9") (name "/A6") (class "Default")
      (node (ref "DD1") (pin "39") (pinfunction "PB3_39") (pintype "passive"))
      (node (ref "R39") (pin "1") (pinfunction "1_1") (pintype "passive"))
    )
    (net (code "10") (name "/Btn") (class "Default")
      (node (ref "C7") (pin "2") (pinfunction "2_2") (pintype "passive"))
      (node (ref "DD1") (pin "25") (pinfunction "PB12_25") (pintype "passive"))
      (node (ref "R19") (pin "2") (pinfunction "2_2") (pintype "passive"))
      (node (ref "R25") (pin "1") (pinfunction "1_1") (pintype "passive"))
    )
    (net (code "11") (name "/Btn_btn") (class "Default")
      (node (ref "R19") (pin "1") (pinfunction "1_1") (pintype "passive"))
      (node (ref "X9") (pin "10") (pinfunction "10_10") (pintype "passive"))
    )
    (net (code "12") (name "/Buzzer") (class "Default")
      (node (ref "DD1") (pin "18") (pinfunction "PB0_18") (pintype "passive"))
      (node (ref "R72") (pin "1") (pinfunction "1_1") (pintype "passive"))
    )
    (net (code "13") (name "/C0") (class "Default")
      (node (ref "DD1") (pin "30") (pinfunction "PA9_30") (pintype "passive"))
      (node (ref "R55") (pin "1") (pinfunction "1_1") (pintype "passive"))
    )
    (net (code "14") (name "/C1") (class "Default")
      (node (ref "DD1") (pin "29") (pinfunction "PA8_29") (pintype "passive"))
      (node (ref "R57") (pin "1") (pinfunction "1_1") (pintype "passive"))
    )
    (net (code "15") (name "/C2") (class "Default")
      (node (ref "DD1") (pin "17") (pinfunction "PA7_17") (pintype "passive"))
      (node (ref "R59") (pin "1") (pinfunction "1_1") (pintype "passive"))
    )
    (net (code "16") (name "/C3") (class "Default")
      (node (ref "DD1") (pin "16") (pinfunction "PA6_16") (pintype "passive"))
      (node (ref "R61") (pin "1") (pinfunction "1_1") (pintype "passive"))
    )
    (net (code "17") (name "/C4") (class "Default")
      (node (ref "DD1") (pin "15") (pinfunction "PA5_15") (pintype "passive"))
      (node (ref "R63") (pin "1") (pinfunction "1_1") (pintype "passive"))
    )
    (net (code "18") (name "/C5") (class "Default")
      (node (ref "DD1") (pin "14") (pinfunction "PA4_14") (pintype "passive"))
      (node (ref "R65") (pin "1") (pinfunction "1_1") (pintype "passive"))
    )
    (net (code "19") (name "/C6") (class "Default")
      (node (ref "DD1") (pin "13") (pinfunction "PA3_13") (pintype "passive"))
      (node (ref "R67") (pin "1") (pinfunction "1_1") (pintype "passive"))
    )
    (net (code "20") (name "/C7") (class "Default")
      (node (ref "DD1") (pin "12") (pinfunction "PA2_12") (pintype "passive"))
      (node (ref "R74") (pin "1") (pinfunction "1_1") (pintype "passive"))
    )
    (net (code "21") (name "/C8") (class "Default")
      (node (ref "DD1") (pin "11") (pinfunction "PA1_11") (pintype "passive"))
      (node (ref "R76") (pin "1") (pinfunction "1_1") (pintype "passive"))
    )
    (net (code "22") (name "/C9") (class "Default")
      (node (ref "DD1") (pin "10") (pinfunction "PA0_10") (pintype "passive"))
      (node (ref "R78") (pin "1") (pinfunction "1_1") (pintype "passive"))
    )
    (net (code "23") (name "/HV1") (class "Default")
      (node (ref "R13") (pin "2") (pinfunction "2_2") (pintype "passive"))
      (node (ref "R14") (pin "2") (pinfunction "2_2") (pintype "passive"))
      (node (ref "R29") (pin "2") (pinfunction "2_2") (pintype "passive"))
      (node (ref "R30") (pin "2") (pinfunction "2_2") (pintype "passive"))
      (node (ref "R48") (pin "1") (pinfunction "1_1") (pintype "passive"))
      (node (ref "R53") (pin "1") (pinfunction "1_1") (pintype "passive"))
      (node (ref "VT16") (pin "3") (pinfunction "C_3") (pintype "passive"))
      (node (ref "VT3") (pin "2") (pinfunction "E_2") (pintype "passive"))
      (node (ref "VT4") (pin "2") (pinfunction "E_2") (pintype "passive"))
      (node (ref "VT8") (pin "2") (pinfunction "E_2") (pintype "passive"))
      (node (ref "VT9") (pin "2") (pinfunction "E_2") (pintype "passive"))
    )
    (net (code "24") (name "/HV2") (class "Default")
      (node (ref "R50") (pin "2") (pinfunction "2_2") (pintype "passive"))
      (node (ref "R51") (pin "2") (pinfunction "2_2") (pintype "passive"))
      (node (ref "R53") (pin "2") (pinfunction "2_2") (pintype "passive"))
      (node (ref "VT13") (pin "2") (pinfunction "E_2") (pintype "passive"))
      (node (ref "VT14") (pin "2") (pinfunction "E_2") (pintype "passive"))
    )
    (net (code "25") (name "/HV_A1") (class "Default")
      (node (ref "VD2") (pin "2") (pinfunction "K_2") (pintype "passive"))
      (node (ref "X2") (pin "1") (pinfunction "1_1") (pintype "passive"))
    )
    (net (code "26") (name "/HV_A2") (class "Default")
      (node (ref "VD3") (pin "2") (pinfunction "K_2") (pintype "passive"))
      (node (ref "X2") (pin "2") (pinfunction "2_2") (pintype "passive"))
    )
    (net (code "27") (name "/HV_A3") (class "Default")
      (node (ref "VD6") (pin "2") (pinfunction "K_2") (pintype "passive"))
      (node (ref "X2") (pin "3") (pinfunction "3_3") (pintype "passive"))
    )
    (net (code "28") (name "/HV_A4") (class "Default")
      (node (ref "VD7") (pin "2") (pinfunction "K_2") (pintype "passive"))
      (node (ref "X2") (pin "4") (pinfunction "4_4") (pintype "passive"))
    )
    (net (code "29") (name "/HV_A5") (class "Default")
      (node (ref "VD9") (pin "2") (pinfunction "K_2") (pintype "passive"))
      (node (ref "X2") (pin "5") (pinfunction "5_5") (pintype "passive"))
    )
    (net (code "30") (name "/HV_A6") (class "Default")
      (node (ref "VD10") (pin "2") (pinfunction "K_2") (pintype "passive"))
      (node (ref "X2") (pin "6") (pinfunction "6_6") (pintype "passive"))
    )
    (net (code "31") (name "/HV_C0") (class "Default")
      (node (ref "VT17") (pin "3") (pinfunction "C_3") (pintype "passive"))
      (node (ref "X2") (pin "7") (pinfunction "7_7") (pintype "passive"))
    )
    (net (code "32") (name "/HV_C1") (class "Default")
      (node (ref "VT18") (pin "3") (pinfunction "C_3") (pintype "passive"))
      (node (ref "X2") (pin "8") (pinfunction "8_8") (pintype "passive"))
    )
    (net (code "33") (name "/HV_C2") (class "Default")
      (node (ref "VT19") (pin "3") (pinfunction "C_3") (pintype "passive"))
      (node (ref "X2") (pin "9") (pinfunction "9_9") (pintype "passive"))
    )
    (net (code "34") (name "/HV_C3") (class "Default")
      (node (ref "VT20") (pin "3") (pinfunction "C_3") (pintype "passive"))
      (node (ref "X2") (pin "10") (pinfunction "10_10") (pintype "passive"))
    )
    (net (code "35") (name "/HV_C4") (class "Default")
      (node (ref "VT21") (pin "3") (pinfunction "C_3") (pintype "passive"))
      (node (ref "X2") (pin "11") (pinfunction "11_11") (pintype "passive"))
    )
    (net (code "36") (name "/HV_C5") (class "Default")
      (node (ref "VT22") (pin "3") (pinfunction "C_3") (pintype "passive"))
      (node (ref "X2") (pin "12") (pinfunction "12_12") (pintype "passive"))
    )
    (net (code "37") (name "/HV_C6") (class "Default")
      (node (ref "VT23") (pin "3") (pinfunction "C_3") (pintype "passive"))
      (node (ref "X2") (pin "13") (pinfunction "13_13") (pintype "passive"))
    )
    (net (code "38") (name "/HV_C7") (class "Default")
      (node (ref "VT25") (pin "3") (pinfunction "C_3") (pintype "passive"))
      (node (ref "X2") (pin "14") (pinfunction "14_14") (pintype "passive"))
    )
    (net (code "39") (name "/HV_C8") (class "Default")
      (node (ref "VT26") (pin "3") (pinfunction "C_3") (pintype "passive"))
      (node (ref "X2") (pin "15") (pinfunction "15_15") (pintype "passive"))
    )
    (net (code "40") (name "/HV_C9") (class "Default")
      (node (ref "VT27") (pin "3") (pinfunction "C_3") (pintype "passive"))
      (node (ref "X2") (pin "16") (pinfunction "16_16") (pintype "passive"))
    )
    (net (code "41") (name "/HV_I1") (class "Default")
      (node (ref "R89") (pin "2") (pinfunction "2_2") (pintype "passive"))
      (node (ref "VT29") (pin "3") (pinfunction "C_3") (pintype "passive"))
    )
    (net (code "42") (name "/HV_I2") (class "Default")
      (node (ref "R70") (pin "2") (pinfunction "2_2") (pintype "passive"))
      (node (ref "VT30") (pin "3") (pinfunction "C_3") (pintype "passive"))
    )
    (net (code "43") (name "/HV_I3") (class "Default")
      (node (ref "R90") (pin "2") (pinfunction "2_2") (pintype "passive"))
      (node (ref "VT31") (pin "3") (pinfunction "C_3") (pintype "passive"))
    )
    (net (code "44") (name "/HV_Point") (class "Default")
      (node (ref "R28") (pin "1") (pinfunction "1_1") (pintype "passive"))
      (node (ref "R33") (pin "1") (pinfunction "1_1") (pintype "passive"))
      (node (ref "R35") (pin "1") (pinfunction "1_1") (pintype "passive"))
      (node (ref "R41") (pin "1") (pinfunction "1_1") (pintype "passive"))
      (node (ref "VT28") (pin "3") (pinfunction "C_3") (pintype "passive"))
    )
    (net (code "45") (name "/I1") (class "Default")
      (node (ref "DD1") (pin "33") (pinfunction "PA12_33") (pintype "passive"))
      (node (ref "R82") (pin "1") (pinfunction "1_1") (pintype "passive"))
    )
    (net (code "46") (name "/I2") (class "Default")
      (node (ref "DD1") (pin "32") (pinfunction "PA11_32") (pintype "passive"))
      (node (ref "R84") (pin "1") (pinfunction "1_1") (pintype "passive"))
    )
    (net (code "47") (name "/I3") (class "Default")
      (node (ref "DD1") (pin "31") (pinfunction "PA10_31") (pintype "passive"))
      (node (ref "R86") (pin "1") (pinfunction "1_1") (pintype "passive"))
    )
    (net (code "48") (name "/Menu") (class "Default")
      (node (ref "C2") (pin "2") (pinfunction "2_2") (pintype "passive"))
      (node (ref "DD1") (pin "27") (pinfunction "PB14_27") (pintype "passive"))
      (node (ref "R5") (pin "2") (pinfunction "2_2") (pintype "passive"))
      (node (ref "R7") (pin "1") (pinfunction "1_1") (pintype "passive"))
    )
    (net (code "49") (name "/Menu_btn") (class "Default")
      (node (ref "R5") (pin "1") (pinfunction "1_1") (pintype "passive"))
      (node (ref "X9") (pin "8") (pinfunction "8_8") (pintype "passive"))
    )
    (net (code "50") (name "/Photo") (class "Default")
      (node (ref "C9") (pin "2") (pinfunction "2_2") (pintype "passive"))
      (node (ref "DD1") (pin "19") (pinfunction "PB1_19") (pintype "passive"))
      (node (ref "R31") (pin "1") (pinfunction "1_1") (pintype "passive"))
      (node (ref "X9") (pin "7") (pinfunction "7_7") (pintype "passive"))
    )
    (net (code "51") (name "/Point") (class "Default")
      (node (ref "DD1") (pin "20") (pinfunction "PB2_20") (pintype "passive"))
      (node (ref "R80") (pin "1") (pinfunction "1_1") (pintype "passive"))
    )
    (net (code "52") (name "/Power_mode") (class "Default")
      (node (ref "DD1") (pin "38") (pinfunction "PA15_38") (pintype "passive"))
      (node (ref "R46") (pin "1") (pinfunction "1_1") (pintype "passive"))
    )
    (net (code "53") (name "/RX") (class "Default")
      (node (ref "DD1") (pin "22") (pinfunction "PB11_22") (pintype "passive"))
      (node (ref "R36") (pin "1") (pinfunction "1_1") (pintype "passive"))
      (node (ref "X7") (pin "3") (pinfunction "3_3") (pintype "passive"))
    )
    (net (code "54") (name "/SWCLK") (class "Default")
      (node (ref "DD1") (pin "37") (pinfunction "PA14_37") (pintype "passive"))
      (node (ref "X8") (pin "3") (pinfunction "SWCLK_3") (pintype "passive"))
    )
    (net (code "55") (name "/SWDIO") (class "Default")
      (node (ref "DD1") (pin "34") (pinfunction "PA13_34") (pintype "passive"))
      (node (ref "X8") (pin "1") (pinfunction "SWDIO_1") (pintype "passive"))
    )
    (net (code "56") (name "/Set") (class "Default")
      (node (ref "C3") (pin "2") (pinfunction "2_2") (pintype "passive"))
      (node (ref "DD1") (pin "26") (pinfunction "PB13_26") (pintype "passive"))
      (node (ref "R15") (pin "2") (pinfunction "2_2") (pintype "passive"))
      (node (ref "R17") (pin "1") (pinfunction "1_1") (pintype "passive"))
    )
    (net (code "57") (name "/Set_btn") (class "Default")
      (node (ref "R15") (pin "1") (pinfunction "1_1") (pintype "passive"))
      (node (ref "X9") (pin "9") (pinfunction "9_9") (pintype "passive"))
    )
    (net (code "58") (name "/TX") (class "Default")
      (node (ref "DD1") (pin "21") (pinfunction "PB10_21") (pintype "passive"))
      (node (ref "R42") (pin "1") (pinfunction "1_1") (pintype "passive"))
      (node (ref "X7") (pin "2") (pinfunction "2_2") (pintype "passive"))
    )
    (net (code "59") (name "GND") (class "Default")
      (node (ref "C1") (pin "1") (pinfunction "1_1") (pintype "passive"))
      (node (ref "C10") (pin "1") (pinfunction "1_1") (pintype "passive"))
      (node (ref "C11") (pin "1") (pinfunction "1_1") (pintype "passive"))
      (node (ref "C12") (pin "1") (pinfunction "1_1") (pintype "passive"))
      (node (ref "C13") (pin "1") (pinfunction "1_1") (pintype "passive"))
      (node (ref "C14") (pin "1") (pinfunction "1_1") (pintype "passive"))
      (node (ref "C15") (pin "1") (pinfunction "1_1") (pintype "passive"))
      (node (ref "C16") (pin "1") (pinfunction "1_1") (pintype "passive"))
      (node (ref "C17") (pin "1") (pinfunction "1_1") (pintype "passive"))
      (node (ref "C18") (pin "1") (pinfunction "1_1") (pintype "passive"))
      (node (ref "C19") (pin "1") (pinfunction "1_1") (pintype "passive"))
      (node (ref "C2") (pin "1") (pinfunction "1_1") (pintype "passive"))
      (node (ref "C20") (pin "1") (pinfunction "1_1") (pintype "passive"))
      (node (ref "C3") (pin "1") (pinfunction "1_1") (pintype "passive"))
      (node (ref "C4") (pin "2") (pinfunction "2_2") (pintype "passive"))
      (node (ref "C5") (pin "1") (pinfunction "1_1") (pintype "passive"))
      (node (ref "C6") (pin "1") (pinfunction "1_1") (pintype "passive"))
      (node (ref "C7") (pin "1") (pinfunction "1_1") (pintype "passive"))
      (node (ref "C8") (pin "2") (pinfunction "2_2") (pintype "passive"))
      (node (ref "C9") (pin "1") (pinfunction "1_1") (pintype "passive"))
      (node (ref "DA1") (pin "4") (pinfunction "GND_4") (pintype "passive"))
      (node (ref "DD1") (pin "23") (pinfunction "Vss1_23") (pintype "passive"))
      (node (ref "DD1") (pin "35") (pinfunction "Vss2_35") (pintype "passive"))
      (node (ref "DD1") (pin "47") (pinfunction "Vss3_47") (pintype "passive"))
      (node (ref "DD1") (pin "8") (pinfunction "Vssa_8") (pintype "passive"))
      (node (ref "GB1") (pin "2") (pinfunction "2_2") (pintype "passive"))
      (node (ref "R16") (pin "2") (pinfunction "2_2") (pintype "passive"))
      (node (ref "R16") (pin "3") (pinfunction "3_3") (pintype "passive"))
      (node (ref "R2") (pin "1") (pinfunction "1_1") (pintype "passive"))
      (node (ref "R21") (pin "1") (pinfunction "1_1") (pintype "passive"))
      (node (ref "R23") (pin "1") (pinfunction "1_1") (pintype "passive"))
      (node (ref "R24") (pin "1") (pinfunction "1_1") (pintype "passive"))
      (node (ref "R38") (pin "1") (pinfunction "1_1") (pintype "passive"))
      (node (ref "R4") (pin "1") (pinfunction "1_1") (pintype "passive"))
      (node (ref "R40") (pin "1") (pinfunction "1_1") (pintype "passive"))
      (node (ref "R47") (pin "1") (pinfunction "1_1") (pintype "passive"))
      (node (ref "R54") (pin "1") (pinfunction "1_1") (pintype "passive"))
      (node (ref "R56") (pin "1") (pinfunction "1_1") (pintype "passive"))
      (node (ref "R58") (pin "1") (pinfunction "1_1") (pintype "passive"))
      (node (ref "R60") (pin "1") (pinfunction "1_1") (pintype "passive"))
      (node (ref "R62") (pin "1") (pinfunction "1_1") (pintype "passive"))
      (node (ref "R64") (pin "1") (pinfunction "1_1") (pintype "passive"))
      (node (ref "R66") (pin "1") (pinfunction "1_1") (pintype "passive"))
      (node (ref "R68") (pin "1") (pinfunction "1_1") (pintype "passive"))
      (node (ref "R75") (pin "1") (pinfunction "1_1") (pintype "passive"))
      (node (ref "R77") (pin "1") (pinfunction "1_1") (pintype "passive"))
      (node (ref "R79") (pin "1") (pinfunction "1_1") (pintype "passive"))
      (node (ref "R81") (pin "1") (pinfunction "1_1") (pintype "passive"))
      (node (ref "R83") (pin "1") (pinfunction "1_1") (pintype "passive"))
      (node (ref "R85") (pin "1") (pinfunction "1_1") (pintype "passive"))
      (node (ref "R87") (pin "1") (pinfunction "1_1") (pintype "passive"))
      (node (ref "R88") (pin "1") (pinfunction "1_1") (pintype "passive"))
      (node (ref "VD1") (pin "4") (pinfunction "-U_4") (pintype "passive"))
      (node (ref "VD5") (pin "1") (pinfunction "A_1") (pintype "passive"))
      (node (ref "VT1") (pin "2") (pinfunction "E_2") (pintype "passive"))
      (node (ref "VT10") (pin "3") (pinfunction "S_3") (pintype "passive"))
      (node (ref "VT11") (pin "2") (pinfunction "E_2") (pintype "passive"))
      (node (ref "VT12") (pin "2") (pinfunction "E_2") (pintype "passive"))
      (node (ref "VT15") (pin "2") (pinfunction "E_2") (pintype "passive"))
      (node (ref "VT17") (pin "2") (pinfunction "E_2") (pintype "passive"))
      (node (ref "VT18") (pin "2") (pinfunction "E_2") (pintype "passive"))
      (node (ref "VT19") (pin "2") (pinfunction "E_2") (pintype "passive"))
      (node (ref "VT2") (pin "2") (pinfunction "E_2") (pintype "passive"))
      (node (ref "VT20") (pin "2") (pinfunction "E_2") (pintype "passive"))
      (node (ref "VT21") (pin "2") (pinfunction "E_2") (pintype "passive"))
      (node (ref "VT22") (pin "2") (pinfunction "E_2") (pintype "passive"))
      (node (ref "VT23") (pin "2") (pinfunction "E_2") (pintype "passive"))
      (node (ref "VT24") (pin "2") (pinfunction "E_2") (pintype "passive"))
      (node (ref "VT25") (pin "2") (pinfunction "E_2") (pintype "passive"))
      (node (ref "VT26") (pin "2") (pinfunction "E_2") (pintype "passive"))
      (node (ref "VT27") (pin "2") (pinfunction "E_2") (pintype "passive"))
      (node (ref "VT28") (pin "2") (pinfunction "E_2") (pintype "passive"))
      (node (ref "VT29") (pin "2") (pinfunction "E_2") (pintype "passive"))
      (node (ref "VT30") (pin "2") (pinfunction "E_2") (pintype "passive"))
      (node (ref "VT31") (pin "2") (pinfunction "E_2") (pintype "passive"))
      (node (ref "VT5") (pin "2") (pinfunction "E_2") (pintype "passive"))
      (node (ref "VT6") (pin "2") (pinfunction "E_2") (pintype "passive"))
      (node (ref "VT7") (pin "3") (pinfunction "C_3") (pintype "passive"))
      (node (ref "X4") (pin "2") (pinfunction "2_2") (pintype "passive"))
      (node (ref "X7") (pin "4") (pinfunction "4_4") (pintype "passive"))
      (node (ref "X8") (pin "4") (pinfunction "GND_4") (pintype "passive"))
      (node (ref "X9") (pin "5") (pinfunction "5_5") (pintype "passive"))
      (node (ref "X9") (pin "6") (pinfunction "6_6") (pintype "passive"))
      (node (ref "ZQ1") (pin "3") (pinfunction "3_3") (pintype "passive"))
    )
    (net (code "60") (name "Net-(BF1--)") (class "Default")
      (node (ref "BF1") (pin "2") (pinfunction "-_2") (pintype "passive"))
      (node (ref "VT24") (pin "3") (pinfunction "C_3") (pintype "passive"))
    )
    (net (code "61") (name "Net-(DA1-DC)") (class "Default")
      (node (ref "DA1") (pin "1") (pinfunction "SC_1") (pintype "passive"))
      (node (ref "DA1") (pin "7") (pinfunction "IPK_7") (pintype "passive"))
      (node (ref "DA1") (pin "8") (pinfunction "DC_8") (pintype "passive"))
      (node (ref "L1") (pin "4") (pinfunction "4_4") (pintype "passive"))
      (node (ref "R6") (pin "2") (pinfunction "2_2") (pintype "passive"))
      (node (ref "R8") (pin "2") (pinfunction "2_2") (pintype "passive"))
    )
    (net (code "62") (name "Net-(DA1-FB)") (class "Default")
      (node (ref "DA1") (pin "5") (pinfunction "FB_5") (pintype "passive"))
      (node (ref "R12") (pin "1") (pinfunction "1_1") (pintype "passive"))
      (node (ref "R9") (pin "2") (pinfunction "2_2") (pintype "passive"))
    )
    (net (code "63") (name "Net-(DA1-SE)") (class "Default")
      (node (ref "DA1") (pin "2") (pinfunction "SE_2") (pintype "passive"))
      (node (ref "R18") (pin "1") (pinfunction "1_1") (pintype "passive"))
    )
    (net (code "64") (name "Net-(DA1-TC)") (class "Default")
      (node (ref "C5") (pin "2") (pinfunction "2_2") (pintype "passive"))
      (node (ref "DA1") (pin "3") (pinfunction "TC_3") (pintype "passive"))
    )
    (net (code "65") (name "Net-(DD1-BOOT0)") (class "Default")
      (node (ref "DD1") (pin "44") (pinfunction "BOOT0_44") (pintype "passive"))
      (node (ref "R54") (pin "2") (pinfunction "2_2") (pintype "passive"))
    )
    (net (code "66") (name "Net-(DD1-NRST)") (class "Default")
      (node (ref "C16") (pin "2") (pinfunction "2_2") (pintype "passive"))
      (node (ref "DD1") (pin "7") (pinfunction "NRST_7") (pintype "passive"))
      (node (ref "R69") (pin "2") (pinfunction "2_2") (pintype "passive"))
    )
    (net (code "67") (name "Net-(DD1-OSC_IN)") (class "Default")
      (node (ref "C20") (pin "2") (pinfunction "2_2") (pintype "passive"))
      (node (ref "DD1") (pin "5") (pinfunction "OSC_IN_5") (pintype "passive"))
      (node (ref "ZQ2") (pin "2") (pinfunction "2_2") (pintype "passive"))
    )
    (net (code "68") (name "Net-(DD1-OSC_OUT)") (class "Default")
      (node (ref "C19") (pin "2") (pinfunction "2_2") (pintype "passive"))
      (node (ref "DD1") (pin "6") (pinfunction "OSC_OUT_6") (pintype "passive"))
      (node (ref "ZQ2") (pin "1") (pinfunction "1_1") (pintype "passive"))
    )
    (net (code "69") (name "Net-(DD1-PC14)") (class "Default")
      (node (ref "C10") (pin "2") (pinfunction "2_2") (pintype "passive"))
      (node (ref "DD1") (pin "3") (pinfunction "PC14_3") (pintype "passive"))
      (node (ref "ZQ1") (pin "1") (pinfunction "1_1") (pintype "passive"))
    )
    (net (code "70") (name "Net-(DD1-PC15)") (class "Default")
      (node (ref "C13") (pin "2") (pinfunction "2_2") (pintype "passive"))
      (node (ref "DD1") (pin "4") (pinfunction "PC15_4") (pintype "passive"))
      (node (ref "ZQ1") (pin "2") (pinfunction "2_2") (pintype "passive"))
    )
    (net (code "71") (name "Net-(DD1-Vbat)") (class "Default")
      (node (ref "C12") (pin "2") (pinfunction "2_2") (pintype "passive"))
      (node (ref "DD1") (pin "1") (pinfunction "Vbat_1") (pintype "passive"))
      (node (ref "GB1") (pin "1") (pinfunction "1_1") (pintype "passive"))
    )
    (net (code "72") (name "Net-(R12-Pad2)") (class "Default")
      (node (ref "R12") (pin "2") (pinfunction "2_2") (pintype "passive"))
      (node (ref "R16") (pin "1") (pinfunction "1_1") (pintype "passive"))
    )
    (net (code "73") (name "Net-(R28-Pad2)") (class "Default")
      (node (ref "R28") (pin "2") (pinfunction "2_2") (pintype "passive"))
      (node (ref "X5") (pin "3") (pinfunction "3_3") (pintype "passive"))
    )
    (net (code "74") (name "Net-(R32-Pad1)") (class "Default")
      (node (ref "R32") (pin "1") (pinfunction "1_1") (pintype "passive"))
      (node (ref "R34") (pin "1") (pinfunction "1_1") (pintype "passive"))
      (node (ref "X5") (pin "1") (pinfunction "1_1") (pintype "passive"))
      (node (ref "X6") (pin "1") (pinfunction "1_1") (pintype "passive"))
    )
    (net (code "75") (name "Net-(R33-Pad2)") (class "Default")
      (node (ref "R33") (pin "2") (pinfunction "2_2") (pintype "passive"))
      (node (ref "X5") (pin "2") (pinfunction "2_2") (pintype "passive"))
    )
    (net (code "76") (name "Net-(R35-Pad2)") (class "Default")
      (node (ref "R35") (pin "2") (pinfunction "2_2") (pintype "passive"))
      (node (ref "X6") (pin "2") (pinfunction "2_2") (pintype "passive"))
    )
    (net (code "77") (name "Net-(R41-Pad2)") (class "Default")
      (node (ref "R41") (pin "2") (pinfunction "2_2") (pintype "passive"))
      (node (ref "X6") (pin "3") (pinfunction "3_3") (pintype "passive"))
    )
    (net (code "78") (name "Net-(R70-Pad1)") (class "Default")
      (node (ref "R70") (pin "1") (pinfunction "1_1") (pintype "passive"))
      (node (ref "X9") (pin "3") (pinfunction "3_3") (pintype "passive"))
    )
    (net (code "79") (name "Net-(R71-Pad1)") (class "Default")
      (node (ref "R71") (pin "1") (pinfunction "1_1") (pintype "passive"))
      (node (ref "R73") (pin "1") (pinfunction "1_1") (pintype "passive"))
      (node (ref "X9") (pin "1") (pinfunction "1_1") (pintype "passive"))
    )
    (net (code "80") (name "Net-(R89-Pad1)") (class "Default")
      (node (ref "R89") (pin "1") (pinfunction "1_1") (pintype "passive"))
      (node (ref "X9") (pin "2") (pinfunction "2_2") (pintype "passive"))
    )
    (net (code "81") (name "Net-(R90-Pad1)") (class "Default")
      (node (ref "R90") (pin "1") (pinfunction "1_1") (pintype "passive"))
      (node (ref "X9") (pin "4") (pinfunction "4_4") (pintype "passive"))
    )
    (net (code "82") (name "Net-(VD1-AC1)") (class "Default")
      (node (ref "VD1") (pin "2") (pinfunction "AC1_2") (pintype "passive"))
      (node (ref "X1") (pin "1") (pinfunction "1_1") (pintype "passive"))
    )
    (net (code "83") (name "Net-(VD1-AC2)") (class "Default")
      (node (ref "VD1") (pin "3") (pinfunction "AC2_3") (pintype "passive"))
      (node (ref "X3") (pin "1") (pinfunction "1_1") (pintype "passive"))
    )
    (net (code "84") (name "Net-(VD2-A)") (class "Default")
      (node (ref "VD2") (pin "1") (pinfunction "A_1") (pintype "passive"))
      (node (ref "VT3") (pin "3") (pinfunction "C_3") (pintype "passive"))
    )
    (net (code "85") (name "Net-(VD3-A)") (class "Default")
      (node (ref "VD3") (pin "1") (pinfunction "A_1") (pintype "passive"))
      (node (ref "VT4") (pin "3") (pinfunction "C_3") (pintype "passive"))
    )
    (net (code "86") (name "Net-(VD4-A)") (class "Default")
      (node (ref "R18") (pin "2") (pinfunction "2_2") (pintype "passive"))
      (node (ref "R24") (pin "2") (pinfunction "2_2") (pintype "passive"))
      (node (ref "VD4") (pin "1") (pinfunction "A_1") (pintype "passive"))
      (node (ref "VT7") (pin "1") (pinfunction "B_1") (pintype "passive"))
    )
    (net (code "87") (name "Net-(VD4-K)") (class "Default")
      (node (ref "VD4") (pin "2") (pinfunction "K_2") (pintype "passive"))
      (node (ref "VD5") (pin "2") (pinfunction "K_2") (pintype "passive"))
      (node (ref "VT10") (pin "1") (pinfunction "G_1") (pintype "passive"))
      (node (ref "VT7") (pin "2") (pinfunction "E_2") (pintype "passive"))
    )
    (net (code "88") (name "Net-(VD6-A)") (class "Default")
      (node (ref "VD6") (pin "1") (pinfunction "A_1") (pintype "passive"))
      (node (ref "VT8") (pin "3") (pinfunction "C_3") (pintype "passive"))
    )
    (net (code "89") (name "Net-(VD7-A)") (class "Default")
      (node (ref "VD7") (pin "1") (pinfunction "A_1") (pintype "passive"))
      (node (ref "VT9") (pin "3") (pinfunction "C_3") (pintype "passive"))
    )
    (net (code "90") (name "Net-(VD8-A)") (class "Default")
      (node (ref "L1") (pin "1") (pinfunction "1_1") (pintype "passive"))
      (node (ref "VD8") (pin "1") (pinfunction "A_1") (pintype "passive"))
      (node (ref "VT10") (pin "2") (pinfunction "D_2") (pintype "passive"))
    )
    (net (code "91") (name "Net-(VD9-A)") (class "Default")
      (node (ref "VD9") (pin "1") (pinfunction "A_1") (pintype "passive"))
      (node (ref "VT13") (pin "3") (pinfunction "C_3") (pintype "passive"))
    )
    (net (code "92") (name "Net-(VD10-A)") (class "Default")
      (node (ref "VD10") (pin "1") (pinfunction "A_1") (pintype "passive"))
      (node (ref "VT14") (pin "3") (pinfunction "C_3") (pintype "passive"))
    )
    (net (code "93") (name "Net-(VT1-B)") (class "Default")
      (node (ref "R1") (pin "2") (pinfunction "2_2") (pintype "passive"))
      (node (ref "R2") (pin "2") (pinfunction "2_2") (pintype "passive"))
      (node (ref "VT1") (pin "1") (pinfunction "B_1") (pintype "passive"))
    )
    (net (code "94") (name "Net-(VT1-C)") (class "Default")
      (node (ref "R10") (pin "1") (pinfunction "1_1") (pintype "passive"))
      (node (ref "VT1") (pin "3") (pinfunction "C_3") (pintype "passive"))
    )
    (net (code "95") (name "Net-(VT2-B)") (class "Default")
      (node (ref "R3") (pin "2") (pinfunction "2_2") (pintype "passive"))
      (node (ref "R4") (pin "2") (pinfunction "2_2") (pintype "passive"))
      (node (ref "VT2") (pin "1") (pinfunction "B_1") (pintype "passive"))
    )
    (net (code "96") (name "Net-(VT2-C)") (class "Default")
      (node (ref "R11") (pin "1") (pinfunction "1_1") (pintype "passive"))
      (node (ref "VT2") (pin "3") (pinfunction "C_3") (pintype "passive"))
    )
    (net (code "97") (name "Net-(VT3-B)") (class "Default")
      (node (ref "R10") (pin "2") (pinfunction "2_2") (pintype "passive"))
      (node (ref "R13") (pin "1") (pinfunction "1_1") (pintype "passive"))
      (node (ref "VT3") (pin "1") (pinfunction "B_1") (pintype "passive"))
    )
    (net (code "98") (name "Net-(VT4-B)") (class "Default")
      (node (ref "R11") (pin "2") (pinfunction "2_2") (pintype "passive"))
      (node (ref "R14") (pin "1") (pinfunction "1_1") (pintype "passive"))
      (node (ref "VT4") (pin "1") (pinfunction "B_1") (pintype "passive"))
    )
    (net (code "99") (name "Net-(VT5-B)") (class "Default")
      (node (ref "R20") (pin "2") (pinfunction "2_2") (pintype "passive"))
      (node (ref "R21") (pin "2") (pinfunction "2_2") (pintype "passive"))
      (node (ref "VT5") (pin "1") (pinfunction "B_1") (pintype "passive"))
    )
    (net (code "100") (name "Net-(VT5-C)") (class "Default")
      (node (ref "R26") (pin "1") (pinfunction "1_1") (pintype "passive"))
      (node (ref "VT5") (pin "3") (pinfunction "C_3") (pintype "passive"))
    )
    (net (code "101") (name "Net-(VT6-B)") (class "Default")
      (node (ref "R22") (pin "2") (pinfunction "2_2") (pintype "passive"))
      (node (ref "R23") (pin "2") (pinfunction "2_2") (pintype "passive"))
      (node (ref "VT6") (pin "1") (pinfunction "B_1") (pintype "passive"))
    )
    (net (code "102") (name "Net-(VT6-C)") (class "Default")
      (node (ref "R27") (pin "1") (pinfunction "1_1") (pintype "passive"))
      (node (ref "VT6") (pin "3") (pinfunction "C_3") (pintype "passive"))
    )
    (net (code "103") (name "Net-(VT8-B)") (class "Default")
      (node (ref "R26") (pin "2") (pinfunction "2_2") (pintype "passive"))
      (node (ref "R29") (pin "1") (pinfunction "1_1") (pintype "passive"))
      (node (ref "VT8") (pin "1") (pinfunction "B_1") (pintype "passive"))
    )
    (net (code "104") (name "Net-(VT9-B)") (class "Default")
      (node (ref "R27") (pin "2") (pinfunction "2_2") (pintype "passive"))
      (node (ref "R30") (pin "1") (pinfunction "1_1") (pintype "passive"))
      (node (ref "VT9") (pin "1") (pinfunction "B_1") (pintype "passive"))
    )
    (net (code "105") (name "Net-(VT11-B)") (class "Default")
      (node (ref "R37") (pin "2") (pinfunction "2_2") (pintype "passive"))
      (node (ref "R38") (pin "2") (pinfunction "2_2") (pintype "passive"))
      (node (ref "VT11") (pin "1") (pinfunction "B_1") (pintype "passive"))
    )
    (net (code "106") (name "Net-(VT11-C)") (class "Default")
      (node (ref "R44") (pin "1") (pinfunction "1_1") (pintype "passive"))
      (node (ref "VT11") (pin "3") (pinfunction "C_3") (pintype "passive"))
    )
    (net (code "107") (name "Net-(VT12-B)") (class "Default")
      (node (ref "R39") (pin "2") (pinfunction "2_2") (pintype "passive"))
      (node (ref "R40") (pin "2") (pinfunction "2_2") (pintype "passive"))
      (node (ref "VT12") (pin "1") (pinfunction "B_1") (pintype "passive"))
    )
    (net (code "108") (name "Net-(VT12-C)") (class "Default")
      (node (ref "R45") (pin "1") (pinfunction "1_1") (pintype "passive"))
      (node (ref "VT12") (pin "3") (pinfunction "C_3") (pintype "passive"))
    )
    (net (code "109") (name "Net-(VT13-B)") (class "Default")
      (node (ref "R44") (pin "2") (pinfunction "2_2") (pintype "passive"))
      (node (ref "R50") (pin "1") (pinfunction "1_1") (pintype "passive"))
      (node (ref "VT13") (pin "1") (pinfunction "B_1") (pintype "passive"))
    )
    (net (code "110") (name "Net-(VT14-B)") (class "Default")
      (node (ref "R45") (pin "2") (pinfunction "2_2") (pintype "passive"))
      (node (ref "R51") (pin "1") (pinfunction "1_1") (pintype "passive"))
      (node (ref "VT14") (pin "1") (pinfunction "B_1") (pintype "passive"))
    )
    (net (code "111") (name "Net-(VT15-B)") (class "Default")
      (node (ref "R46") (pin "2") (pinfunction "2_2") (pintype "passive"))
      (node (ref "R47") (pin "2") (pinfunction "2_2") (pintype "passive"))
      (node (ref "VT15") (pin "1") (pinfunction "B_1") (pintype "passive"))
    )
    (net (code "112") (name "Net-(VT15-C)") (class "Default")
      (node (ref "R52") (pin "1") (pinfunction "1_1") (pintype "passive"))
      (node (ref "VT15") (pin "3") (pinfunction "C_3") (pintype "passive"))
    )
    (net (code "113") (name "Net-(VT16-B)") (class "Default")
      (node (ref "R49") (pin "2") (pinfunction "2_2") (pintype "passive"))
      (node (ref "R52") (pin "2") (pinfunction "2_2") (pintype "passive"))
      (node (ref "VT16") (pin "1") (pinfunction "B_1") (pintype "passive"))
    )
    (net (code "114") (name "Net-(VT16-E)") (class "Default")
      (node (ref "R43") (pin "2") (pinfunction "2_2") (pintype "passive"))
      (node (ref "R48") (pin "2") (pinfunction "2_2") (pintype "passive"))
      (node (ref "R49") (pin "1") (pinfunction "1_1") (pintype "passive"))
      (node (ref "VT16") (pin "2") (pinfunction "E_2") (pintype "passive"))
    )
    (net (code "115") (name "Net-(VT17-B)") (class "Default")
      (node (ref "R55") (pin "2") (pinfunction "2_2") (pintype "passive"))
      (node (ref "R56") (pin "2") (pinfunction "2_2") (pintype "passive"))
      (node (ref "VT17") (pin "1") (pinfunction "B_1") (pintype "passive"))
    )
    (net (code "116") (name "Net-(VT18-B)") (class "Default")
      (node (ref "R57") (pin "2") (pinfunction "2_2") (pintype "passive"))
      (node (ref "R58") (pin "2") (pinfunction "2_2") (pintype "passive"))
      (node (ref "VT18") (pin "1") (pinfunction "B_1") (pintype "passive"))
    )
    (net (code "117") (name "Net-(VT19-B)") (class "Default")
      (node (ref "R59") (pin "2") (pinfunction "2_2") (pintype "passive"))
      (node (ref "R60") (pin "2") (pinfunction "2_2") (pintype "passive"))
      (node (ref "VT19") (pin "1") (pinfunction "B_1") (pintype "passive"))
    )
    (net (code "118") (name "Net-(VT20-B)") (class "Default")
      (node (ref "R61") (pin "2") (pinfunction "2_2") (pintype "passive"))
      (node (ref "R62") (pin "2") (pinfunction "2_2") (pintype "passive"))
      (node (ref "VT20") (pin "1") (pinfunction "B_1") (pintype "passive"))
    )
    (net (code "119") (name "Net-(VT21-B)") (class "Default")
      (node (ref "R63") (pin "2") (pinfunction "2_2") (pintype "passive"))
      (node (ref "R64") (pin "2") (pinfunction "2_2") (pintype "passive"))
      (node (ref "VT21") (pin "1") (pinfunction "B_1") (pintype "passive"))
    )
    (net (code "120") (name "Net-(VT22-B)") (class "Default")
      (node (ref "R65") (pin "2") (pinfunction "2_2") (pintype "passive"))
      (node (ref "R66") (pin "2") (pinfunction "2_2") (pintype "passive"))
      (node (ref "VT22") (pin "1") (pinfunction "B_1") (pintype "passive"))
    )
    (net (code "121") (name "Net-(VT23-B)") (class "Default")
      (node (ref "R67") (pin "2") (pinfunction "2_2") (pintype "passive"))
      (node (ref "R68") (pin "2") (pinfunction "2_2") (pintype "passive"))
      (node (ref "VT23") (pin "1") (pinfunction "B_1") (pintype "passive"))
    )
    (net (code "122") (name "Net-(VT24-B)") (class "Default")
      (node (ref "R72") (pin "2") (pinfunction "2_2") (pintype "passive"))
      (node (ref "R88") (pin "2") (pinfunction "2_2") (pintype "passive"))
      (node (ref "VT24") (pin "1") (pinfunction "B_1") (pintype "passive"))
    )
    (net (code "123") (name "Net-(VT25-B)") (class "Default")
      (node (ref "R74") (pin "2") (pinfunction "2_2") (pintype "passive"))
      (node (ref "R75") (pin "2") (pinfunction "2_2") (pintype "passive"))
      (node (ref "VT25") (pin "1") (pinfunction "B_1") (pintype "passive"))
    )
    (net (code "124") (name "Net-(VT26-B)") (class "Default")
      (node (ref "R76") (pin "2") (pinfunction "2_2") (pintype "passive"))
      (node (ref "R77") (pin "2") (pinfunction "2_2") (pintype "passive"))
      (node (ref "VT26") (pin "1") (pinfunction "B_1") (pintype "passive"))
    )
    (net (code "125") (name "Net-(VT27-B)") (class "Default")
      (node (ref "R78") (pin "2") (pinfunction "2_2") (pintype "passive"))
      (node (ref "R79") (pin "2") (pinfunction "2_2") (pintype "passive"))
      (node (ref "VT27") (pin "1") (pinfunction "B_1") (pintype "passive"))
    )
    (net (code "126") (name "Net-(VT28-B)") (class "Default")
      (node (ref "R80") (pin "2") (pinfunction "2_2") (pintype "passive"))
      (node (ref "R81") (pin "2") (pinfunction "2_2") (pintype "passive"))
      (node (ref "VT28") (pin "1") (pinfunction "B_1") (pintype "passive"))
    )
    (net (code "127") (name "Net-(VT29-B)") (class "Default")
      (node (ref "R82") (pin "2") (pinfunction "2_2") (pintype "passive"))
      (node (ref "R83") (pin "2") (pinfunction "2_2") (pintype "passive"))
      (node (ref "VT29") (pin "1") (pinfunction "B_1") (pintype "passive"))
    )
    (net (code "128") (name "Net-(VT30-B)") (class "Default")
      (node (ref "R84") (pin "2") (pinfunction "2_2") (pintype "passive"))
      (node (ref "R85") (pin "2") (pinfunction "2_2") (pintype "passive"))
      (node (ref "VT30") (pin "1") (pinfunction "B_1") (pintype "passive"))
    )
    (net (code "129") (name "Net-(VT31-B)") (class "Default")
      (node (ref "R86") (pin "2") (pinfunction "2_2") (pintype "passive"))
      (node (ref "R87") (pin "2") (pinfunction "2_2") (pintype "passive"))
      (node (ref "VT31") (pin "1") (pinfunction "B_1") (pintype "passive"))
    )
    (net (code "130") (name "unconnected-(DD1-PB9-Pad46)") (class "Default")
      (node (ref "DD1") (pin "46") (pinfunction "PB9_46") (pintype "passive"))
    )
    (net (code "131") (name "unconnected-(DD1-PB15-Pad28)") (class "Default")
      (node (ref "DD1") (pin "28") (pinfunction "PB15_28") (pintype "passive"))
    )
    (net (code "132") (name "unconnected-(DD1-PC13-Pad2)") (class "Default")
      (node (ref "DD1") (pin "2") (pinfunction "PC13_2") (pintype "passive"))
    )
  )
)
